# funpam-eagle.net
KiCad netlist of a schematic drawn in EAGLE
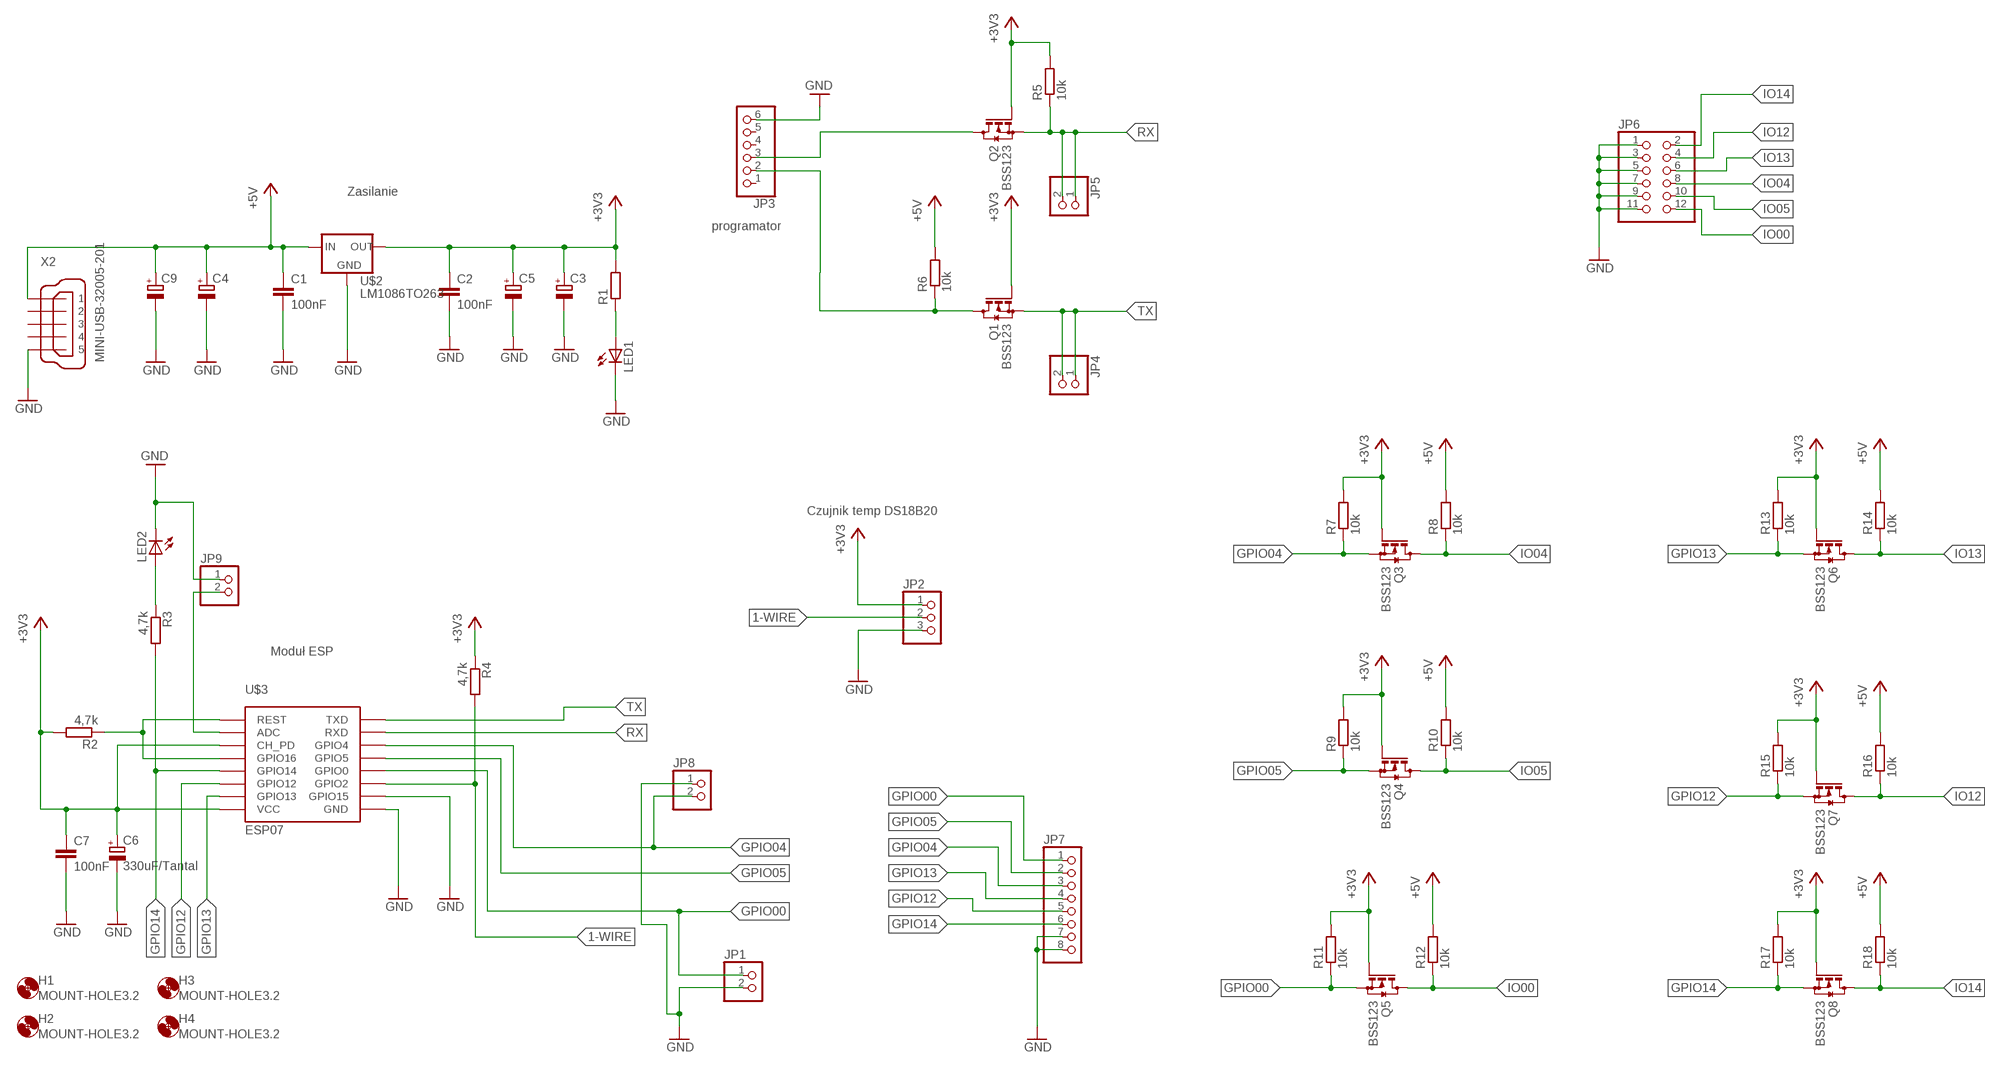
[diagram p0: schematic, sheet 1]

(export (version "E")
  (design (tool "Eeschema 10.0.6"))
  (components
    (comp (ref "C1")
      (value "100nF")
      (footprint "eagle-import:C1206")
      (libsource (lib "eagle-import") (part "C-EUC1206"))
    )
    (comp (ref "C2")
      (value "100nF")
      (footprint "eagle-import:C1206")
      (libsource (lib "eagle-import") (part "C-EUC1206"))
    )
    (comp (ref "C3")
      (value "CPOL-EU153CLV-0605")
      (footprint "eagle-import:153CLV-0605")
      (libsource (lib "eagle-import") (part "CPOL-EU153CLV-0605"))
    )
    (comp (ref "C4")
      (value "CPOL-EU153CLV-1010")
      (footprint "eagle-import:153CLV-1010")
      (libsource (lib "eagle-import") (part "CPOL-EU153CLV-1010"))
    )
    (comp (ref "C5")
      (value "CPOL-EU153CLV-1010")
      (footprint "eagle-import:153CLV-1010")
      (libsource (lib "eagle-import") (part "CPOL-EU153CLV-1010"))
    )
    (comp (ref "C6")
      (value "330uF/Tantal")
      (footprint "eagle-import:SMC_D")
      (libsource (lib "eagle-import") (part "CPOL-EUSMCD"))
    )
    (comp (ref "C7")
      (value "100nF")
      (footprint "eagle-import:C1206")
      (libsource (lib "eagle-import") (part "C-EUC1206"))
    )
    (comp (ref "C9")
      (value "CPOL-EU153CLV-1010")
      (footprint "eagle-import:153CLV-1010")
      (libsource (lib "eagle-import") (part "CPOL-EU153CLV-1010"))
    )
    (comp (ref "H1")
      (value "MOUNT-HOLE3.2")
      (footprint "eagle-import:3,2")
      (libsource (lib "eagle-import") (part "MOUNT-HOLE3.2"))
    )
    (comp (ref "H2")
      (value "MOUNT-HOLE3.2")
      (footprint "eagle-import:3,2")
      (libsource (lib "eagle-import") (part "MOUNT-HOLE3.2"))
    )
    (comp (ref "H3")
      (value "MOUNT-HOLE3.2")
      (footprint "eagle-import:3,2")
      (libsource (lib "eagle-import") (part "MOUNT-HOLE3.2"))
    )
    (comp (ref "H4")
      (value "MOUNT-HOLE3.2")
      (footprint "eagle-import:3,2")
      (libsource (lib "eagle-import") (part "MOUNT-HOLE3.2"))
    )
    (comp (ref "JP1")
      (value "PINHD-1X2")
      (footprint "eagle-import:1X02")
      (libsource (lib "eagle-import") (part "PINHD-1X2"))
    )
    (comp (ref "JP2")
      (value "PINHD-1X3")
      (footprint "eagle-import:1X03")
      (libsource (lib "eagle-import") (part "PINHD-1X3"))
    )
    (comp (ref "JP3")
      (value "PINHD-1X6")
      (footprint "eagle-import:1X06")
      (libsource (lib "eagle-import") (part "PINHD-1X6"))
    )
    (comp (ref "JP4")
      (value "PINHD-1X2")
      (footprint "eagle-import:1X02")
      (libsource (lib "eagle-import") (part "PINHD-1X2"))
    )
    (comp (ref "JP5")
      (value "PINHD-1X2")
      (footprint "eagle-import:1X02")
      (libsource (lib "eagle-import") (part "PINHD-1X2"))
    )
    (comp (ref "JP6")
      (value "PINHD-2X6")
      (footprint "eagle-import:2X06")
      (libsource (lib "eagle-import") (part "PINHD-2X6"))
    )
    (comp (ref "JP7")
      (value "PINHD-1X8")
      (footprint "eagle-import:1X08")
      (libsource (lib "eagle-import") (part "PINHD-1X8"))
    )
    (comp (ref "JP8")
      (value "PINHD-1X2")
      (footprint "eagle-import:1X02")
      (libsource (lib "eagle-import") (part "PINHD-1X2"))
    )
    (comp (ref "JP9")
      (value "PINHD-1X2")
      (footprint "eagle-import:1X02")
      (libsource (lib "eagle-import") (part "PINHD-1X2"))
    )
    (comp (ref "LED1")
      (value "LED3MM")
      (footprint "eagle-import:LED3MM")
      (libsource (lib "eagle-import") (part "LED3MM"))
    )
    (comp (ref "LED2")
      (value "LEDCHIPLED_1206")
      (footprint "eagle-import:CHIPLED_1206")
      (libsource (lib "eagle-import") (part "LEDCHIPLED_1206"))
    )
    (comp (ref "Q1")
      (value "BSS123")
      (footprint "eagle-import:SOT23")
      (libsource (lib "eagle-import") (part "BSS123"))
    )
    (comp (ref "Q2")
      (value "BSS123")
      (footprint "eagle-import:SOT23")
      (libsource (lib "eagle-import") (part "BSS123"))
    )
    (comp (ref "Q3")
      (value "BSS123")
      (footprint "eagle-import:SOT23")
      (libsource (lib "eagle-import") (part "BSS123"))
    )
    (comp (ref "Q4")
      (value "BSS123")
      (footprint "eagle-import:SOT23")
      (libsource (lib "eagle-import") (part "BSS123"))
    )
    (comp (ref "Q5")
      (value "BSS123")
      (footprint "eagle-import:SOT23")
      (libsource (lib "eagle-import") (part "BSS123"))
    )
    (comp (ref "Q6")
      (value "BSS123")
      (footprint "eagle-import:SOT23")
      (libsource (lib "eagle-import") (part "BSS123"))
    )
    (comp (ref "Q7")
      (value "BSS123")
      (footprint "eagle-import:SOT23")
      (libsource (lib "eagle-import") (part "BSS123"))
    )
    (comp (ref "Q8")
      (value "BSS123")
      (footprint "eagle-import:SOT23")
      (libsource (lib "eagle-import") (part "BSS123"))
    )
    (comp (ref "R1")
      (value "R-EU_R1206")
      (footprint "eagle-import:R1206")
      (libsource (lib "eagle-import") (part "R-EU_R1206"))
    )
    (comp (ref "R2")
      (value "4,7k")
      (footprint "eagle-import:R1206")
      (libsource (lib "eagle-import") (part "R-EU_R1206"))
    )
    (comp (ref "R3")
      (value "4,7k")
      (footprint "eagle-import:R1206")
      (libsource (lib "eagle-import") (part "R-EU_R1206"))
    )
    (comp (ref "R4")
      (value "4,7k")
      (footprint "eagle-import:R1206")
      (libsource (lib "eagle-import") (part "R-EU_R1206"))
    )
    (comp (ref "R5")
      (value "10k")
      (footprint "eagle-import:R1206")
      (libsource (lib "eagle-import") (part "R-EU_R1206"))
    )
    (comp (ref "R6")
      (value "10k")
      (footprint "eagle-import:R1206")
      (libsource (lib "eagle-import") (part "R-EU_R1206"))
    )
    (comp (ref "R7")
      (value "10k")
      (footprint "eagle-import:R1206")
      (libsource (lib "eagle-import") (part "R-EU_R1206"))
    )
    (comp (ref "R8")
      (value "10k")
      (footprint "eagle-import:R1206")
      (libsource (lib "eagle-import") (part "R-EU_R1206"))
    )
    (comp (ref "R9")
      (value "10k")
      (footprint "eagle-import:R1206")
      (libsource (lib "eagle-import") (part "R-EU_R1206"))
    )
    (comp (ref "R10")
      (value "10k")
      (footprint "eagle-import:R1206")
      (libsource (lib "eagle-import") (part "R-EU_R1206"))
    )
    (comp (ref "R11")
      (value "10k")
      (footprint "eagle-import:R1206")
      (libsource (lib "eagle-import") (part "R-EU_R1206"))
    )
    (comp (ref "R12")
      (value "10k")
      (footprint "eagle-import:R1206")
      (libsource (lib "eagle-import") (part "R-EU_R1206"))
    )
    (comp (ref "R13")
      (value "10k")
      (footprint "eagle-import:R1206")
      (libsource (lib "eagle-import") (part "R-EU_R1206"))
    )
    (comp (ref "R14")
      (value "10k")
      (footprint "eagle-import:R1206")
      (libsource (lib "eagle-import") (part "R-EU_R1206"))
    )
    (comp (ref "R15")
      (value "10k")
      (footprint "eagle-import:R1206")
      (libsource (lib "eagle-import") (part "R-EU_R1206"))
    )
    (comp (ref "R16")
      (value "10k")
      (footprint "eagle-import:R1206")
      (libsource (lib "eagle-import") (part "R-EU_R1206"))
    )
    (comp (ref "R17")
      (value "10k")
      (footprint "eagle-import:R1206")
      (libsource (lib "eagle-import") (part "R-EU_R1206"))
    )
    (comp (ref "R18")
      (value "10k")
      (footprint "eagle-import:R1206")
      (libsource (lib "eagle-import") (part "R-EU_R1206"))
    )
    (comp (ref "U$2")
      (value "LM1086TO263")
      (footprint "eagle-import:TO263")
      (libsource (lib "eagle-import") (part "LM1086TO263"))
    )
    (comp (ref "U$3")
      (value "ESP07")
      (footprint "eagle-import:ESP07")
      (libsource (lib "eagle-import") (part "ESP07"))
    )
    (comp (ref "X2")
      (value "MINI-USB-32005-201")
      (footprint "eagle-import:32005-201")
      (libsource (lib "eagle-import") (part "MINI-USB-32005-201"))
    )
  )
  (nets
    (net (code "1") (name "+3V3") (class "Default")
      (node (ref "C2") (pin "1") (pinfunction "1_1") (pintype "passive"))
      (node (ref "C3") (pin "+") (pinfunction "+_+") (pintype "passive"))
      (node (ref "C5") (pin "+") (pinfunction "+_+") (pintype "passive"))
      (node (ref "C6") (pin "+") (pinfunction "+_+") (pintype "passive"))
      (node (ref "C7") (pin "1") (pinfunction "1_1") (pintype "passive"))
      (node (ref "JP2") (pin "1") (pinfunction "1_1") (pintype "passive"))
      (node (ref "Q1") (pin "1") (pinfunction "G_1") (pintype "passive"))
      (node (ref "Q2") (pin "1") (pinfunction "G_1") (pintype "passive"))
      (node (ref "Q3") (pin "1") (pinfunction "G_1") (pintype "passive"))
      (node (ref "Q4") (pin "1") (pinfunction "G_1") (pintype "passive"))
      (node (ref "Q5") (pin "1") (pinfunction "G_1") (pintype "passive"))
      (node (ref "Q6") (pin "1") (pinfunction "G_1") (pintype "passive"))
      (node (ref "Q7") (pin "1") (pinfunction "G_1") (pintype "passive"))
      (node (ref "Q8") (pin "1") (pinfunction "G_1") (pintype "passive"))
      (node (ref "R1") (pin "2") (pinfunction "2_2") (pintype "passive"))
      (node (ref "R11") (pin "2") (pinfunction "2_2") (pintype "passive"))
      (node (ref "R13") (pin "2") (pinfunction "2_2") (pintype "passive"))
      (node (ref "R15") (pin "2") (pinfunction "2_2") (pintype "passive"))
      (node (ref "R17") (pin "2") (pinfunction "2_2") (pintype "passive"))
      (node (ref "R2") (pin "2") (pinfunction "2_2") (pintype "passive"))
      (node (ref "R4") (pin "1") (pinfunction "1_1") (pintype "passive"))
      (node (ref "R5") (pin "2") (pinfunction "2_2") (pintype "passive"))
      (node (ref "R7") (pin "2") (pinfunction "2_2") (pintype "passive"))
      (node (ref "R9") (pin "2") (pinfunction "2_2") (pintype "passive"))
      (node (ref "U$2") (pin "2") (pinfunction "OUT_2") (pintype "passive"))
      (node (ref "U$3") (pin "CH_PD") (pinfunction "CH_PD_CH_PD") (pintype "bidirectional"))
      (node (ref "U$3") (pin "VCC") (pinfunction "VCC_VCC") (pintype "bidirectional"))
    )
    (net (code "2") (name "+5V") (class "Default")
      (node (ref "C1") (pin "1") (pinfunction "1_1") (pintype "passive"))
      (node (ref "C4") (pin "+") (pinfunction "+_+") (pintype "passive"))
      (node (ref "C9") (pin "+") (pinfunction "+_+") (pintype "passive"))
      (node (ref "R10") (pin "2") (pinfunction "2_2") (pintype "passive"))
      (node (ref "R12") (pin "2") (pinfunction "2_2") (pintype "passive"))
      (node (ref "R14") (pin "2") (pinfunction "2_2") (pintype "passive"))
      (node (ref "R16") (pin "2") (pinfunction "2_2") (pintype "passive"))
      (node (ref "R18") (pin "2") (pinfunction "2_2") (pintype "passive"))
      (node (ref "R6") (pin "2") (pinfunction "2_2") (pintype "passive"))
      (node (ref "R8") (pin "2") (pinfunction "2_2") (pintype "passive"))
      (node (ref "U$2") (pin "3") (pinfunction "IN_3") (pintype "input"))
      (node (ref "X2") (pin "1") (pinfunction "1_1") (pintype "passive"))
    )
    (net (code "3") (name "1-WIRE") (class "Default")
      (node (ref "JP2") (pin "2") (pinfunction "2_2") (pintype "passive"))
      (node (ref "R4") (pin "2") (pinfunction "2_2") (pintype "passive"))
      (node (ref "U$3") (pin "GPIO2") (pinfunction "GPIO2_GPIO2") (pintype "bidirectional"))
    )
    (net (code "4") (name "GND") (class "Default")
      (node (ref "C1") (pin "2") (pinfunction "2_2") (pintype "passive"))
      (node (ref "C2") (pin "2") (pinfunction "2_2") (pintype "passive"))
      (node (ref "C3") (pin "-") (pinfunction "-_-") (pintype "passive"))
      (node (ref "C4") (pin "-") (pinfunction "-_-") (pintype "passive"))
      (node (ref "C5") (pin "-") (pinfunction "-_-") (pintype "passive"))
      (node (ref "C6") (pin "-") (pinfunction "-_-") (pintype "passive"))
      (node (ref "C7") (pin "2") (pinfunction "2_2") (pintype "passive"))
      (node (ref "C9") (pin "-") (pinfunction "-_-") (pintype "passive"))
      (node (ref "JP1") (pin "2") (pinfunction "2_2") (pintype "passive"))
      (node (ref "JP2") (pin "3") (pinfunction "3_3") (pintype "passive"))
      (node (ref "JP3") (pin "6") (pinfunction "6_6") (pintype "passive"))
      (node (ref "JP6") (pin "1") (pinfunction "1_1") (pintype "passive"))
      (node (ref "JP6") (pin "11") (pinfunction "11_11") (pintype "passive"))
      (node (ref "JP6") (pin "3") (pinfunction "3_3") (pintype "passive"))
      (node (ref "JP6") (pin "5") (pinfunction "5_5") (pintype "passive"))
      (node (ref "JP6") (pin "7") (pinfunction "7_7") (pintype "passive"))
      (node (ref "JP6") (pin "9") (pinfunction "9_9") (pintype "passive"))
      (node (ref "JP7") (pin "7") (pinfunction "7_7") (pintype "passive"))
      (node (ref "JP7") (pin "8") (pinfunction "8_8") (pintype "passive"))
      (node (ref "JP8") (pin "1") (pinfunction "1_1") (pintype "passive"))
      (node (ref "JP9") (pin "1") (pinfunction "1_1") (pintype "passive"))
      (node (ref "LED1") (pin "K") (pinfunction "C_K") (pintype "passive"))
      (node (ref "LED2") (pin "C") (pinfunction "C_C") (pintype "passive"))
      (node (ref "U$2") (pin "1") (pinfunction "GND_1") (pintype "input"))
      (node (ref "U$3") (pin "GND") (pinfunction "GND_GND") (pintype "bidirectional"))
      (node (ref "U$3") (pin "GPIO15") (pinfunction "GPIO15_GPIO15") (pintype "bidirectional"))
      (node (ref "X2") (pin "5") (pinfunction "5_5") (pintype "passive"))
    )
    (net (code "5") (name "GPIO00") (class "Default")
      (node (ref "JP1") (pin "1") (pinfunction "1_1") (pintype "passive"))
      (node (ref "JP7") (pin "1") (pinfunction "1_1") (pintype "passive"))
      (node (ref "Q5") (pin "2") (pinfunction "S_2") (pintype "passive"))
      (node (ref "R11") (pin "1") (pinfunction "1_1") (pintype "passive"))
      (node (ref "U$3") (pin "GPIO0") (pinfunction "GPIO0_GPIO0") (pintype "bidirectional"))
    )
    (net (code "6") (name "GPIO04") (class "Default")
      (node (ref "JP7") (pin "3") (pinfunction "3_3") (pintype "passive"))
      (node (ref "JP8") (pin "2") (pinfunction "2_2") (pintype "passive"))
      (node (ref "Q3") (pin "2") (pinfunction "S_2") (pintype "passive"))
      (node (ref "R7") (pin "1") (pinfunction "1_1") (pintype "passive"))
      (node (ref "U$3") (pin "GPIO4") (pinfunction "GPIO4_GPIO4") (pintype "bidirectional"))
    )
    (net (code "7") (name "GPIO05") (class "Default")
      (node (ref "JP7") (pin "2") (pinfunction "2_2") (pintype "passive"))
      (node (ref "Q4") (pin "2") (pinfunction "S_2") (pintype "passive"))
      (node (ref "R9") (pin "1") (pinfunction "1_1") (pintype "passive"))
      (node (ref "U$3") (pin "GPIO5") (pinfunction "GPIO5_GPIO5") (pintype "bidirectional"))
    )
    (net (code "8") (name "GPIO12") (class "Default")
      (node (ref "JP7") (pin "5") (pinfunction "5_5") (pintype "passive"))
      (node (ref "Q7") (pin "2") (pinfunction "S_2") (pintype "passive"))
      (node (ref "R15") (pin "1") (pinfunction "1_1") (pintype "passive"))
      (node (ref "U$3") (pin "GPIO12") (pinfunction "GPIO12_GPIO12") (pintype "bidirectional"))
    )
    (net (code "9") (name "GPIO13") (class "Default")
      (node (ref "JP7") (pin "4") (pinfunction "4_4") (pintype "passive"))
      (node (ref "Q6") (pin "2") (pinfunction "S_2") (pintype "passive"))
      (node (ref "R13") (pin "1") (pinfunction "1_1") (pintype "passive"))
      (node (ref "U$3") (pin "GPIO13") (pinfunction "GPIO13_GPIO13") (pintype "bidirectional"))
    )
    (net (code "10") (name "GPIO14") (class "Default")
      (node (ref "JP7") (pin "6") (pinfunction "6_6") (pintype "passive"))
      (node (ref "Q8") (pin "2") (pinfunction "S_2") (pintype "passive"))
      (node (ref "R17") (pin "1") (pinfunction "1_1") (pintype "passive"))
      (node (ref "R3") (pin "2") (pinfunction "2_2") (pintype "passive"))
      (node (ref "U$3") (pin "GPIO14") (pinfunction "GPIO14_GPIO14") (pintype "bidirectional"))
    )
    (net (code "11") (name "IO00") (class "Default")
      (node (ref "JP6") (pin "12") (pinfunction "12_12") (pintype "passive"))
      (node (ref "Q5") (pin "3") (pinfunction "D_3") (pintype "passive"))
      (node (ref "R12") (pin "1") (pinfunction "1_1") (pintype "passive"))
    )
    (net (code "12") (name "IO04") (class "Default")
      (node (ref "JP6") (pin "8") (pinfunction "8_8") (pintype "passive"))
      (node (ref "Q3") (pin "3") (pinfunction "D_3") (pintype "passive"))
      (node (ref "R8") (pin "1") (pinfunction "1_1") (pintype "passive"))
    )
    (net (code "13") (name "IO05") (class "Default")
      (node (ref "JP6") (pin "10") (pinfunction "10_10") (pintype "passive"))
      (node (ref "Q4") (pin "3") (pinfunction "D_3") (pintype "passive"))
      (node (ref "R10") (pin "1") (pinfunction "1_1") (pintype "passive"))
    )
    (net (code "14") (name "IO12") (class "Default")
      (node (ref "JP6") (pin "4") (pinfunction "4_4") (pintype "passive"))
      (node (ref "Q7") (pin "3") (pinfunction "D_3") (pintype "passive"))
      (node (ref "R16") (pin "1") (pinfunction "1_1") (pintype "passive"))
    )
    (net (code "15") (name "IO13") (class "Default")
      (node (ref "JP6") (pin "6") (pinfunction "6_6") (pintype "passive"))
      (node (ref "Q6") (pin "3") (pinfunction "D_3") (pintype "passive"))
      (node (ref "R14") (pin "1") (pinfunction "1_1") (pintype "passive"))
    )
    (net (code "16") (name "IO14") (class "Default")
      (node (ref "JP6") (pin "2") (pinfunction "2_2") (pintype "passive"))
      (node (ref "Q8") (pin "3") (pinfunction "D_3") (pintype "passive"))
      (node (ref "R18") (pin "1") (pinfunction "1_1") (pintype "passive"))
    )
    (net (code "17") (name "Net-(JP9-Pad2)") (class "Default")
      (node (ref "JP9") (pin "2") (pinfunction "2_2") (pintype "passive"))
      (node (ref "U$3") (pin "ADC") (pinfunction "ADC_ADC") (pintype "bidirectional"))
    )
    (net (code "18") (name "Net-(LED1-PadA)") (class "Default")
      (node (ref "LED1") (pin "A") (pinfunction "A_A") (pintype "passive"))
      (node (ref "R1") (pin "1") (pinfunction "1_1") (pintype "passive"))
    )
    (net (code "19") (name "Net-(LED2-PadA)") (class "Default")
      (node (ref "LED2") (pin "A") (pinfunction "A_A") (pintype "passive"))
      (node (ref "R3") (pin "1") (pinfunction "1_1") (pintype "passive"))
    )
    (net (code "20") (name "Net-(Q1-D)") (class "Default")
      (node (ref "JP3") (pin "2") (pinfunction "2_2") (pintype "passive"))
      (node (ref "Q1") (pin "3") (pinfunction "D_3") (pintype "passive"))
      (node (ref "R6") (pin "1") (pinfunction "1_1") (pintype "passive"))
    )
    (net (code "21") (name "Net-(Q2-D)") (class "Default")
      (node (ref "JP3") (pin "3") (pinfunction "3_3") (pintype "passive"))
      (node (ref "Q2") (pin "3") (pinfunction "D_3") (pintype "passive"))
    )
    (net (code "22") (name "Net-(R2-Pad1)") (class "Default")
      (node (ref "R2") (pin "1") (pinfunction "1_1") (pintype "passive"))
      (node (ref "U$3") (pin "GPIO16") (pinfunction "GPIO16_GPIO16") (pintype "bidirectional"))
      (node (ref "U$3") (pin "REST") (pinfunction "REST_REST") (pintype "bidirectional"))
    )
    (net (code "23") (name "RX") (class "Default")
      (node (ref "JP5") (pin "1") (pinfunction "1_1") (pintype "passive"))
      (node (ref "JP5") (pin "2") (pinfunction "2_2") (pintype "passive"))
      (node (ref "Q2") (pin "2") (pinfunction "S_2") (pintype "passive"))
      (node (ref "R5") (pin "1") (pinfunction "1_1") (pintype "passive"))
      (node (ref "U$3") (pin "RXD") (pinfunction "RXD_RXD") (pintype "bidirectional"))
    )
    (net (code "24") (name "TX") (class "Default")
      (node (ref "JP4") (pin "1") (pinfunction "1_1") (pintype "passive"))
      (node (ref "JP4") (pin "2") (pinfunction "2_2") (pintype "passive"))
      (node (ref "Q1") (pin "2") (pinfunction "S_2") (pintype "passive"))
      (node (ref "U$3") (pin "TXD") (pinfunction "TXD_TXD") (pintype "bidirectional"))
    )
    (net (code "25") (name "unconnected-(JP3-Pad1)") (class "Default")
      (node (ref "JP3") (pin "1") (pinfunction "1_1") (pintype "passive"))
    )
    (net (code "26") (name "unconnected-(JP3-Pad4)") (class "Default")
      (node (ref "JP3") (pin "4") (pinfunction "4_4") (pintype "passive"))
    )
    (net (code "27") (name "unconnected-(JP3-Pad5)") (class "Default")
      (node (ref "JP3") (pin "5") (pinfunction "5_5") (pintype "passive"))
    )
    (net (code "28") (name "unconnected-(X2-Pad2)") (class "Default")
      (node (ref "X2") (pin "2") (pinfunction "2_2") (pintype "passive"))
    )
    (net (code "29") (name "unconnected-(X2-Pad3)") (class "Default")
      (node (ref "X2") (pin "3") (pinfunction "3_3") (pintype "passive"))
    )
    (net (code "30") (name "unconnected-(X2-Pad4)") (class "Default")
      (node (ref "X2") (pin "4") (pinfunction "4_4") (pintype "passive"))
    )
  )
)
